# RS485.net
KiCad netlist of a schematic drawn in Altium Designer
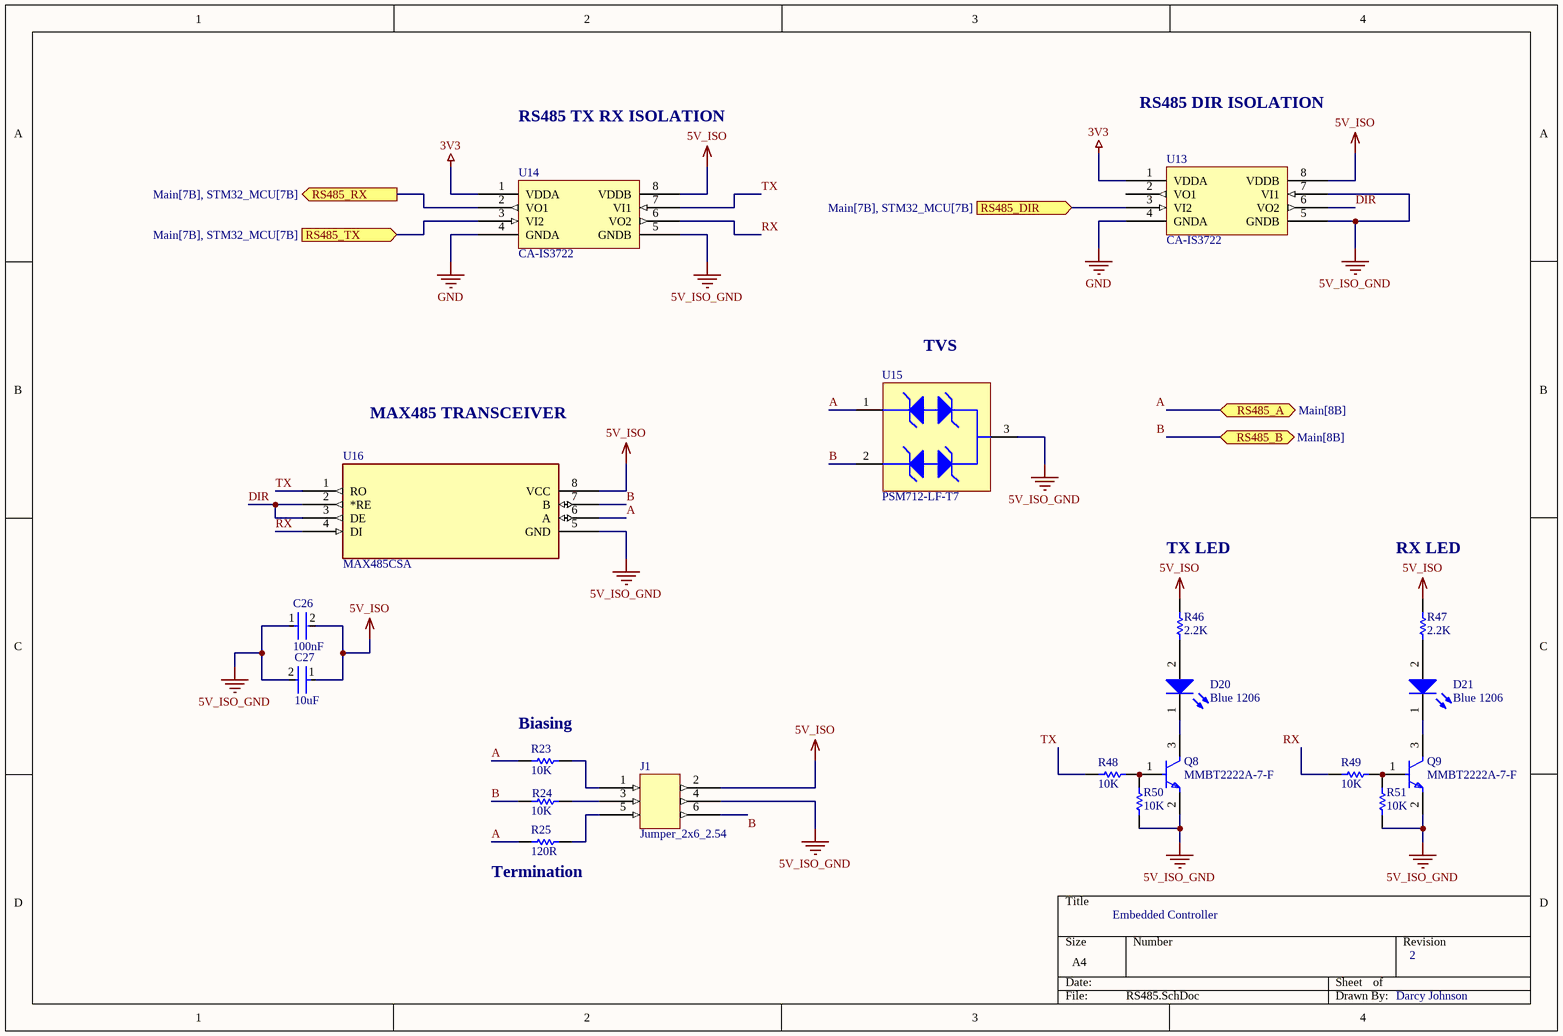
[diagram p0: RS485.SchDoc]

(export (version "E")
  (design (tool "Eeschema 10.0.6"))
  (components
    (comp (ref "C26")
      (value "100nF")
      (footprint "FP-CGA3E-0_3-0_1-IPC_A")
      (description "Cap Ceramic 100nF 50V X7R 10% Pad SMD 0603 +125°C Automotive T/R")
      (fields (field (name "TOLERANCE") "10%") (field (name "VOLTAGE") "50V"))
      (libsource (lib "Altium Content Vault") (part "b4654b650e69147ec39a6b967a45e02"))
    )
    (comp (ref "C27")
      (value "10uF")
      (footprint "FP-GRM188-0_1-e0_2_0_55-IPC_A")
      (description "Chip Multilayer Ceramic Capacitors for General Purpose, 0603, 10uF, X5R, 15%, 20%, 6.3V")
      (fields (field (name "VOLTAGE") "6.3V") (field (name "TOLERANCE") "20%"))
      (libsource (lib "Altium Content Vault") (part "02cd4be3c70576c341d710602a673aa"))
    )
    (comp (ref "D20")
      (value "Blue 1206")
      (footprint "WL-SMCW_1206_150120xx75000")
      (description "WL-SMCW SMT Mono-Color Chip LED Waterclear")
      (libsource (lib "Altium Content Vault") (part "LED_Blue_2A-1K"))
    )
    (comp (ref "D21")
      (value "Blue 1206")
      (footprint "WL-SMCW_1206_150120xx75000")
      (description "WL-SMCW SMT Mono-Color Chip LED Waterclear")
      (libsource (lib "Altium Content Vault") (part "LED_Blue_2A-1K"))
    )
    (comp (ref "J1")
      (value "Jumper_2x6_2.54")
      (footprint "Jumper_2x6_2.54")
      (libsource (lib "Jumper_2x6_2.54") (part "Jumper_2x6_2.54"))
    )
    (comp (ref "Q8")
      (value "MMBT2222A-7-F")
      (footprint "FP-SOT23-IPC_A")
      (description "TRANS NPN 40V 0.6A SMD SOT23-3")
      (fields (field (name "VOLTAGE") "40V"))
      (libsource (lib "Altium Content Vault") (part "b44e953556f554d0102664c7d152cb4"))
    )
    (comp (ref "Q9")
      (value "MMBT2222A-7-F")
      (footprint "FP-SOT23-IPC_A")
      (description "TRANS NPN 40V 0.6A SMD SOT23-3")
      (fields (field (name "VOLTAGE") "40V"))
      (libsource (lib "Altium Content Vault") (part "b44e953556f554d0102664c7d152cb4"))
    )
    (comp (ref "R23")
      (value "10K")
      (footprint "RESC1609X55X30LL15T15")
      (description "Chip Resistor, 10 KOhm, +/- 1%, 0.1 W, -55 to 155 degC, 0603 (1608 Metric), RoHS, Tape and Reel")
      (fields (field (name "TOLERANCE") "1%") (field (name "MANUFACTURER") "Panasonic"))
      (libsource (lib "Altium Content Vault") (part "RES-2"))
    )
    (comp (ref "R24")
      (value "10K")
      (footprint "RESC1609X55X30LL15T15")
      (description "Chip Resistor, 10 KOhm, +/- 1%, 0.1 W, -55 to 155 degC, 0603 (1608 Metric), RoHS, Tape and Reel")
      (fields (field (name "TOLERANCE") "1%") (field (name "MANUFACTURER") "Panasonic"))
      (libsource (lib "Altium Content Vault") (part "RES-2"))
    )
    (comp (ref "R25")
      (value "120R")
      (footprint "RESC1609X55X30ML15T15")
      (description "Chip Resistor, 120 Ohm, +/- 1%, 0.1 W, -55 to 155 degC, 0603 (1608 Metric), RoHS, Tape and Reel")
      (fields (field (name "TOLERANCE") "1%") (field (name "MANUFACTURER") "Panasonic"))
      (libsource (lib "Altium Content Vault") (part "RES-2"))
    )
    (comp (ref "R46")
      (value "2.2K")
      (footprint "RESC1608X55X30NL15T15")
      (fields (field (name "TOLERANCE") "5%"))
      (libsource (lib "Altium Content Vault") (part "RES-2"))
    )
    (comp (ref "R47")
      (value "2.2K")
      (footprint "RESC1608X55X30NL15T15")
      (fields (field (name "TOLERANCE") "5%"))
      (libsource (lib "Altium Content Vault") (part "RES-2"))
    )
    (comp (ref "R48")
      (value "10K")
      (footprint "RESC1609X55X30LL15T15")
      (description "Chip Resistor, 10 KOhm, +/- 1%, 0.1 W, -55 to 155 degC, 0603 (1608 Metric), RoHS, Tape and Reel")
      (fields (field (name "TOLERANCE") "1%") (field (name "MANUFACTURER") "Panasonic"))
      (libsource (lib "Altium Content Vault") (part "RES-2"))
    )
    (comp (ref "R49")
      (value "10K")
      (footprint "RESC1609X55X30LL15T15")
      (description "Chip Resistor, 10 KOhm, +/- 1%, 0.1 W, -55 to 155 degC, 0603 (1608 Metric), RoHS, Tape and Reel")
      (fields (field (name "TOLERANCE") "1%") (field (name "MANUFACTURER") "Panasonic"))
      (libsource (lib "Altium Content Vault") (part "RES-2"))
    )
    (comp (ref "R50")
      (value "10K")
      (footprint "RESC1609X55X30LL15T15")
      (description "Chip Resistor, 10 KOhm, +/- 1%, 0.1 W, -55 to 155 degC, 0603 (1608 Metric), RoHS, Tape and Reel")
      (fields (field (name "TOLERANCE") "1%") (field (name "MANUFACTURER") "Panasonic"))
      (libsource (lib "Altium Content Vault") (part "RES-2"))
    )
    (comp (ref "R51")
      (value "10K")
      (footprint "RESC1609X55X30LL15T15")
      (description "Chip Resistor, 10 KOhm, +/- 1%, 0.1 W, -55 to 155 degC, 0603 (1608 Metric), RoHS, Tape and Reel")
      (fields (field (name "TOLERANCE") "1%") (field (name "MANUFACTURER") "Panasonic"))
      (libsource (lib "Altium Content Vault") (part "RES-2"))
    )
    (comp (ref "U13")
      (value "CA-IS3722")
      (footprint "CA-IS3722HS")
      (description "Dual Channel Standard Digital Isolators")
      (libsource (lib "CA-IS3722HS") (part "CA-IS3722"))
    )
    (comp (ref "U14")
      (value "CA-IS3722")
      (footprint "CA-IS3722HS")
      (description "Dual Channel Standard Digital Isolators")
      (libsource (lib "CA-IS3722HS") (part "CA-IS3722"))
    )
    (comp (ref "U15")
      (value "PSM712-LF-T7")
      (footprint "PRKT-SOT23-3_V")
      (fields (field (name "MANUFACTURER") "Protek Devices") (field (name "VOLTAGE") "12V"))
      (libsource (lib "Altium Content Vault") (part "PRTK-PSM712-SOT23-3"))
    )
    (comp (ref "U16")
      (value "MAX485CSA")
      (footprint "21-0041B_8")
      (description "Low-Power, Slew-Rate-Limited RS-485/RS-422 Transceivers")
      (fields (field (name "MF") "Analog Devices") (field (name "MP") "MAX485CSA+"))
      (libsource (lib "MAX485CSA") (part "MAX485CSA"))
    )
  )
  (nets
    (net (code "1") (name "/A") (class "Default")
      (node (ref "R23") (pin "2") (pinfunction "2_2") (pintype "passive"))
      (node (ref "R25") (pin "1") (pinfunction "1_1") (pintype "passive"))
      (node (ref "U15") (pin "1") (pinfunction "1_1") (pintype "passive"))
      (node (ref "U16") (pin "6") (pinfunction "A_6") (pintype "bidirectional"))
    )
    (net (code "2") (name "/B") (class "Default")
      (node (ref "J1") (pin "6") (pintype "output"))
      (node (ref "R24") (pin "2") (pinfunction "2_2") (pintype "passive"))
      (node (ref "U15") (pin "2") (pinfunction "2_2") (pintype "passive"))
      (node (ref "U16") (pin "7") (pinfunction "B_7") (pintype "bidirectional"))
    )
    (net (code "3") (name "/DIR") (class "Default")
      (node (ref "U13") (pin "6") (pinfunction "VO2_6") (pintype "output"))
      (node (ref "U16") (pin "2") (pinfunction "*RE_2") (pintype "output"))
      (node (ref "U16") (pin "3") (pinfunction "DE_3") (pintype "output"))
    )
    (net (code "4") (name "/RS485_DIR") (class "Default")
      (node (ref "U13") (pin "3") (pinfunction "VI2_3") (pintype "input"))
    )
    (net (code "5") (name "/RS485_RX") (class "Default")
      (node (ref "U14") (pin "2") (pinfunction "VO1_2") (pintype "output"))
    )
    (net (code "6") (name "/RS485_TX") (class "Default")
      (node (ref "U14") (pin "3") (pinfunction "VI2_3") (pintype "input"))
    )
    (net (code "7") (name "/RX") (class "Default")
      (node (ref "R49") (pin "2") (pinfunction "2_2") (pintype "passive"))
      (node (ref "U14") (pin "6") (pinfunction "VO2_6") (pintype "output"))
      (node (ref "U16") (pin "4") (pinfunction "DI_4") (pintype "input"))
    )
    (net (code "8") (name "/TX") (class "Default")
      (node (ref "R48") (pin "2") (pinfunction "2_2") (pintype "passive"))
      (node (ref "U14") (pin "7") (pinfunction "VI1_7") (pintype "input"))
      (node (ref "U16") (pin "1") (pinfunction "RO_1") (pintype "output"))
    )
    (net (code "9") (name "3V3") (class "Default")
      (node (ref "U13") (pin "1") (pinfunction "VDDA_1") (pintype "power_in"))
      (node (ref "U14") (pin "1") (pinfunction "VDDA_1") (pintype "power_in"))
    )
    (net (code "10") (name "5V_ISO") (class "Default")
      (node (ref "C26") (pin "2") (pinfunction "2_2") (pintype "passive"))
      (node (ref "C27") (pin "1") (pinfunction "1_1") (pintype "passive"))
      (node (ref "J1") (pin "2") (pintype "output"))
      (node (ref "R46") (pin "1") (pinfunction "1_1") (pintype "passive"))
      (node (ref "R47") (pin "1") (pinfunction "1_1") (pintype "passive"))
      (node (ref "U13") (pin "8") (pinfunction "VDDB_8") (pintype "power_in"))
      (node (ref "U14") (pin "8") (pinfunction "VDDB_8") (pintype "power_in"))
      (node (ref "U16") (pin "8") (pinfunction "VCC_8") (pintype "power_in"))
    )
    (net (code "11") (name "5V_ISO_GND") (class "Default")
      (node (ref "C26") (pin "1") (pinfunction "1_1") (pintype "passive"))
      (node (ref "C27") (pin "2") (pinfunction "2_2") (pintype "passive"))
      (node (ref "J1") (pin "4") (pintype "output"))
      (node (ref "Q8") (pin "2") (pinfunction "E_2") (pintype "passive"))
      (node (ref "Q9") (pin "2") (pinfunction "E_2") (pintype "passive"))
      (node (ref "R50") (pin "1") (pinfunction "1_1") (pintype "passive"))
      (node (ref "R51") (pin "1") (pinfunction "1_1") (pintype "passive"))
      (node (ref "U13") (pin "5") (pinfunction "GNDB_5") (pintype "power_in"))
      (node (ref "U13") (pin "7") (pinfunction "VI1_7") (pintype "input"))
      (node (ref "U14") (pin "5") (pinfunction "GNDB_5") (pintype "power_in"))
      (node (ref "U15") (pin "3") (pinfunction "3_3") (pintype "passive"))
      (node (ref "U16") (pin "5") (pinfunction "GND_5") (pintype "power_in"))
    )
    (net (code "12") (name "GND") (class "Default")
      (node (ref "U13") (pin "4") (pinfunction "GNDA_4") (pintype "power_in"))
      (node (ref "U14") (pin "4") (pinfunction "GNDA_4") (pintype "power_in"))
    )
    (net (code "13") (name "Net-(D20-A)") (class "Default")
      (node (ref "D20") (pin "2") (pinfunction "A_2") (pintype "passive"))
      (node (ref "R46") (pin "2") (pinfunction "2_2") (pintype "passive"))
    )
    (net (code "14") (name "Net-(D20-K)") (class "Default")
      (node (ref "D20") (pin "1") (pinfunction "K_1") (pintype "passive"))
      (node (ref "Q8") (pin "3") (pinfunction "C_3") (pintype "passive"))
    )
    (net (code "15") (name "Net-(D21-A)") (class "Default")
      (node (ref "D21") (pin "2") (pinfunction "A_2") (pintype "passive"))
      (node (ref "R47") (pin "2") (pinfunction "2_2") (pintype "passive"))
    )
    (net (code "16") (name "Net-(D21-K)") (class "Default")
      (node (ref "D21") (pin "1") (pinfunction "K_1") (pintype "passive"))
      (node (ref "Q9") (pin "3") (pinfunction "C_3") (pintype "passive"))
    )
    (net (code "17") (name "Net-(J1-Pad1)") (class "Default")
      (node (ref "J1") (pin "1") (pintype "input"))
      (node (ref "R23") (pin "1") (pinfunction "1_1") (pintype "passive"))
    )
    (net (code "18") (name "Net-(J1-Pad3)") (class "Default")
      (node (ref "J1") (pin "3") (pintype "input"))
      (node (ref "R24") (pin "1") (pinfunction "1_1") (pintype "passive"))
    )
    (net (code "19") (name "Net-(J1-Pad5)") (class "Default")
      (node (ref "J1") (pin "5") (pintype "input"))
      (node (ref "R25") (pin "2") (pinfunction "2_2") (pintype "passive"))
    )
    (net (code "20") (name "Net-(Q8-B)") (class "Default")
      (node (ref "Q8") (pin "1") (pinfunction "B_1") (pintype "passive"))
      (node (ref "R48") (pin "1") (pinfunction "1_1") (pintype "passive"))
      (node (ref "R50") (pin "2") (pinfunction "2_2") (pintype "passive"))
    )
    (net (code "21") (name "Net-(Q9-B)") (class "Default")
      (node (ref "Q9") (pin "1") (pinfunction "B_1") (pintype "passive"))
      (node (ref "R49") (pin "1") (pinfunction "1_1") (pintype "passive"))
      (node (ref "R51") (pin "2") (pinfunction "2_2") (pintype "passive"))
    )
    (net (code "22") (name "unconnected-(U13-VO1-Pad2)") (class "Default")
      (node (ref "U13") (pin "2") (pinfunction "VO1_2") (pintype "output"))
    )
  )
)
